# sensor-5.net
KiCad netlist of a schematic drawn in Altium Designer
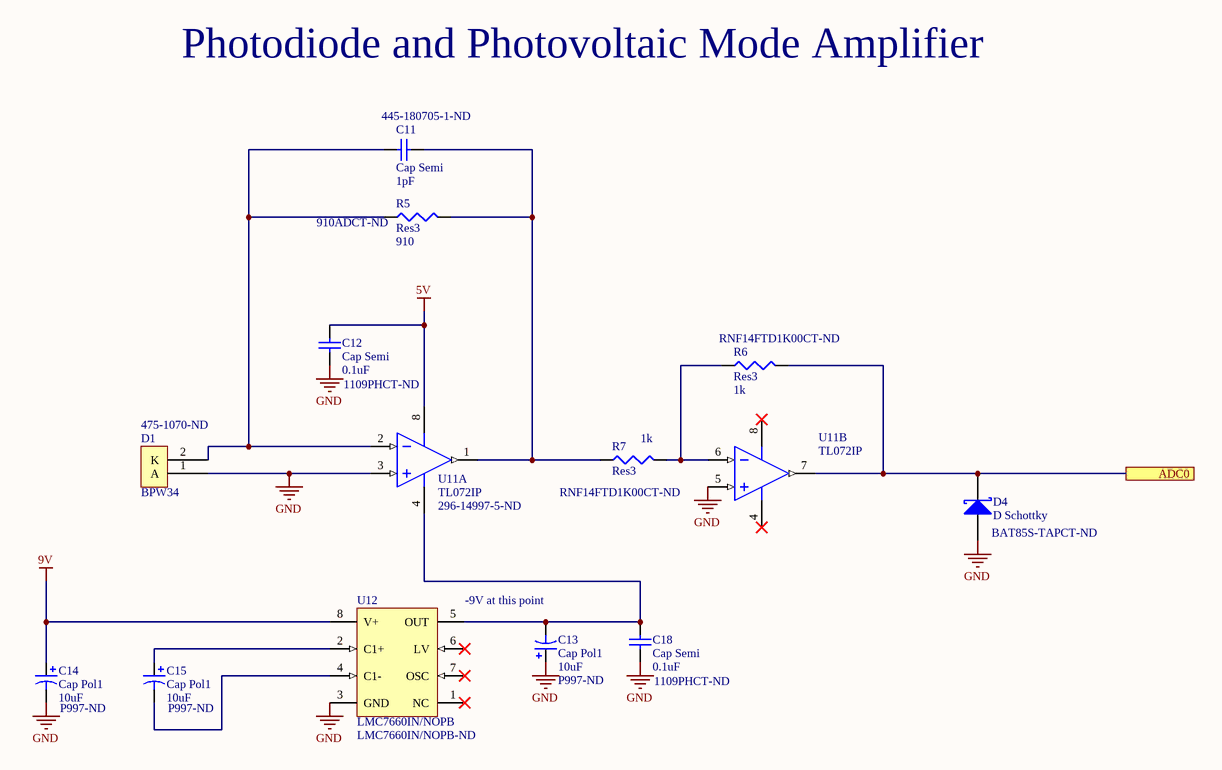
[diagram p0: sensor-5.SchDoc]

(export (version "E")
  (design (tool "Eeschema 10.0.6"))
  (components
    (comp (ref "C11")
      (value "Cap Semi")
      (footprint "FA28C0G1H010CNU06")
      (description "Capacitor (Semiconductor SIM Model)")
      (fields
        (field (name "ALTIUM_VALUE") "1pF")
        (field (name "SUPPLIER PART NUMBER 1") "445-180705-1-ND")
        (field (name "MANUFACTURER") "TDK")
        (field (name "MANUFACTURER PART NUMBER") "FA28C0G1H010CNU06")
        (field (name "PUBLISHER") "Altium Limited")
      )
      (libsource (lib "Miscellaneous Devices") (part "Cap Semi"))
    )
    (comp (ref "C12")
      (value "Cap Semi")
      (footprint "A104K15X7RF5TAA")
      (description "Capacitor (Semiconductor SIM Model)")
      (fields
        (field (name "ALTIUM_VALUE") "0.1uF")
        (field (name "SUPPLIER PART NUMBER 1") "1109PHCT-ND")
        (field (name "MANUFACTURER") "Vishay BCcomponents")
        (field (name "MANUFACTURER PART NUMBER") "A104K15X7RF5TAA")
        (field (name "PUBLISHER") "Altium Limited")
      )
      (libsource (lib "Miscellaneous Devices") (part "Cap Semi"))
    )
    (comp (ref "C13")
      (value "Cap Pol1")
      (footprint "ECE-A1HKS100")
      (description "Polarized Capacitor (Radial)")
      (fields
        (field (name "ALTIUM_VALUE") "10uF")
        (field (name "SUPPLIER PART NUMBER 1") "P997-ND")
        (field (name "MANUFACTURER") "Panasonic")
        (field (name "MANUFACTURER PART NUMBER") "ECE-A1HKS100")
        (field (name "PUBLISHER") "Altium Limited")
      )
      (libsource (lib "Miscellaneous Devices") (part "Cap Pol1"))
    )
    (comp (ref "C14")
      (value "Cap Pol1")
      (footprint "ECE-A1HKS100")
      (description "Polarized Capacitor (Radial)")
      (fields
        (field (name "ALTIUM_VALUE") "10uF")
        (field (name "SUPPLIER PART NUMBER 1") "P997-ND")
        (field (name "MANUFACTURER") "Panasonic")
        (field (name "MANUFACTURER PART NUMBER") "ECE-A1HKS100")
        (field (name "PUBLISHER") "Altium Limited")
      )
      (libsource (lib "Miscellaneous Devices") (part "Cap Pol1"))
    )
    (comp (ref "C15")
      (value "Cap Pol1")
      (footprint "ECE-A1HKS100")
      (description "Polarized Capacitor (Radial)")
      (fields
        (field (name "ALTIUM_VALUE") "10uF")
        (field (name "SUPPLIER PART NUMBER 1") "P997-ND")
        (field (name "MANUFACTURER") "Panasonic")
        (field (name "MANUFACTURER PART NUMBER") "ECE-A1HKS100")
        (field (name "PUBLISHER") "Altium Limited")
      )
      (libsource (lib "Miscellaneous Devices") (part "Cap Pol1"))
    )
    (comp (ref "C18")
      (value "Cap Semi")
      (footprint "A104K15X7RF5TAA")
      (description "Capacitor (Semiconductor SIM Model)")
      (fields
        (field (name "ALTIUM_VALUE") "0.1uF")
        (field (name "SUPPLIER PART NUMBER 1") "1109PHCT-ND")
        (field (name "MANUFACTURER") "Vishay BCcomponents")
        (field (name "MANUFACTURER PART NUMBER") "A104K15X7RF5TAA")
        (field (name "PUBLISHER") "Altium Limited")
      )
      (libsource (lib "Miscellaneous Devices") (part "Cap Semi"))
    )
    (comp (ref "D1")
      (value "BPW34")
      (footprint "BPW34")
      (fields
        (field (name "SUPPLIER PART NUMBER 1") "475-1070-ND")
        (field (name "MANUFACTURER") "Osram Opto")
      )
      (libsource (lib "osram") (part "BPW34"))
    )
    (comp (ref "D4")
      (value "D Schottky")
      (footprint "BAT85S-TAP")
      (description "Schottky Diode")
      (fields
        (field (name "SUPPLIER PART NUMBER 1") "BAT85S-TAPCT-ND")
        (field (name "MANUFACTURER") "Vishay")
        (field (name "MANUFACTURER PART NUMBER") "BAT85S-TAP")
        (field (name "PUBLISHER") "Altium Limited")
      )
      (libsource (lib "Miscellaneous Devices") (part "D Schottky"))
    )
    (comp (ref "R5")
      (value "Res3")
      (footprint "MFP-25BRD52-910R")
      (description "Resistor")
      (fields
        (field (name "ALTIUM_VALUE") "910")
        (field (name "SUPPLIER PART NUMBER 1") "910ADCT-ND")
        (field (name "MANUFACTURER") "Yageo")
        (field (name "MANUFACTURER PART NUMBER") "MFP-25BRD52-910R")
        (field (name "PUBLISHER") "Altium Limited")
      )
      (libsource (lib "Miscellaneous Devices") (part "Res3"))
    )
    (comp (ref "R6")
      (value "Res3")
      (footprint "RNF14FTD1K00")
      (description "Resistor")
      (fields
        (field (name "ALTIUM_VALUE") "1k")
        (field (name "SUPPLIER PART NUMBER 1") "RNF14FTD1K00CT-ND")
        (field (name "MANUFACTURER") "Stackpole Electronics")
        (field (name "MANUFACTURER PART NUMBER") "RNF14FTD1K00")
        (field (name "PUBLISHER") "Altium Limited")
      )
      (libsource (lib "Miscellaneous Devices") (part "Res3"))
    )
    (comp (ref "R7")
      (value "Res3")
      (footprint "RNF14FTD1K00")
      (description "Resistor")
      (fields
        (field (name "ALTIUM_VALUE") "1k")
        (field (name "SUPPLIER PART NUMBER 1") "RNF14FTD1K00CT-ND")
        (field (name "MANUFACTURER") "Stackpole Electronics")
        (field (name "MANUFACTURER PART NUMBER") "RNF14FTD1K00")
        (field (name "PUBLISHER") "Altium Limited")
      )
      (libsource (lib "Miscellaneous Devices") (part "Res3"))
    )
    (comp (ref "U11")
      (value "TL072IP")
      (footprint "P0008A")
      (fields
        (field (name "MANUFACTURER") "Texas Instruments")
        (field (name "SUPPLIER PART NUMBER 1") "296-14997-5-ND")
      )
      (libsource (lib "Altium Content Vault") (part "TI-AMP-D6-2-8_D"))
    )
    (comp (ref "U12")
      (value "LMC7660IN/NOPB")
      (footprint "P0008A")
      (description "Switched Capacitor Voltage Converter, 8-pin MDIP, Pb-Free")
      (fields
        (field (name "MANUFACTURER") "Texas Instruments")
        (field (name "SUPPLIER PART NUMBER 1") "LMC7660IN/NOPB-ND")
      )
      (libsource (lib "Altium Content Vault") (part "PM-CHP-LMC7660IM-8"))
    )
  )
  (nets
    (net (code "1") (name "/ADC0") (class "Default")
      (node (ref "D4") (pin "2") (pinfunction "K_2") (pintype "passive"))
      (node (ref "R6") (pin "2") (pinfunction "2_2") (pintype "passive"))
      (node (ref "U11") (pin "7") (pinfunction "OUT2_7") (pintype "output"))
    )
    (net (code "2") (name "5V") (class "Default")
      (node (ref "C12") (pin "2") (pinfunction "2_2") (pintype "passive"))
      (node (ref "U11") (pin "8") (pinfunction "VCC+_8") (pintype "power_in"))
    )
    (net (code "3") (name "9V") (class "Default")
      (node (ref "C14") (pin "1") (pinfunction "1_1") (pintype "passive"))
      (node (ref "U12") (pin "8") (pinfunction "V+_8") (pintype "power_in"))
    )
    (net (code "4") (name "GND") (class "Default")
      (node (ref "C12") (pin "1") (pinfunction "1_1") (pintype "passive"))
      (node (ref "C13") (pin "1") (pinfunction "1_1") (pintype "passive"))
      (node (ref "C14") (pin "2") (pinfunction "2_2") (pintype "passive"))
      (node (ref "C18") (pin "1") (pinfunction "1_1") (pintype "passive"))
      (node (ref "D1") (pin "1") (pinfunction "A_1") (pintype "passive"))
      (node (ref "D4") (pin "1") (pinfunction "A_1") (pintype "passive"))
      (node (ref "U11") (pin "3") (pinfunction "IN1+_3") (pintype "input"))
      (node (ref "U11") (pin "5") (pinfunction "IN2+_5") (pintype "input"))
      (node (ref "U12") (pin "3") (pinfunction "GND_3") (pintype "power_in"))
    )
    (net (code "5") (name "Net-(D1-K)") (class "Default")
      (node (ref "C11") (pin "1") (pinfunction "1_1") (pintype "passive"))
      (node (ref "D1") (pin "2") (pinfunction "K_2") (pintype "passive"))
      (node (ref "R5") (pin "1") (pinfunction "1_1") (pintype "passive"))
      (node (ref "U11") (pin "2") (pinfunction "IN1-_2") (pintype "input"))
    )
    (net (code "6") (name "Net-(U11A-OUT1)") (class "Default")
      (node (ref "C11") (pin "2") (pinfunction "2_2") (pintype "passive"))
      (node (ref "R5") (pin "2") (pinfunction "2_2") (pintype "passive"))
      (node (ref "R7") (pin "1") (pinfunction "1_1") (pintype "passive"))
      (node (ref "U11") (pin "1") (pinfunction "OUT1_1") (pintype "output"))
    )
    (net (code "7") (name "Net-(U11A-VCC-)") (class "Default")
      (node (ref "C13") (pin "2") (pinfunction "2_2") (pintype "passive"))
      (node (ref "C18") (pin "2") (pinfunction "2_2") (pintype "passive"))
      (node (ref "U11") (pin "4") (pinfunction "VCC-_4") (pintype "power_in"))
      (node (ref "U12") (pin "5") (pinfunction "OUT_5") (pintype "power_in"))
    )
    (net (code "8") (name "Net-(U11B-IN2-)") (class "Default")
      (node (ref "R6") (pin "1") (pinfunction "1_1") (pintype "passive"))
      (node (ref "R7") (pin "2") (pinfunction "2_2") (pintype "passive"))
      (node (ref "U11") (pin "6") (pinfunction "IN2-_6") (pintype "input"))
    )
    (net (code "9") (name "Net-(U12-C1+)") (class "Default")
      (node (ref "C15") (pin "1") (pinfunction "1_1") (pintype "passive"))
      (node (ref "U12") (pin "2") (pinfunction "C1+_2") (pintype "input"))
    )
    (net (code "10") (name "Net-(U12-C1-)") (class "Default")
      (node (ref "C15") (pin "2") (pinfunction "2_2") (pintype "passive"))
      (node (ref "U12") (pin "4") (pinfunction "C1-_4") (pintype "input"))
    )
    (net (code "11") (name "unconnected-(U11B-VCC+-Pad8)") (class "Default")
      (node (ref "U11") (pin "8") (pinfunction "VCC+_8") (pintype "power_in+no_connect"))
    )
    (net (code "12") (name "unconnected-(U11B-VCC--Pad4)") (class "Default")
      (node (ref "U11") (pin "4") (pinfunction "VCC-_4") (pintype "power_in+no_connect"))
    )
    (net (code "13") (name "unconnected-(U12-LV-Pad6)") (class "Default")
      (node (ref "U12") (pin "6") (pinfunction "LV_6") (pintype "input+no_connect"))
    )
    (net (code "14") (name "unconnected-(U12-NC-Pad1)") (class "Default")
      (node (ref "U12") (pin "1") (pinfunction "NC_1") (pintype "passive+no_connect"))
    )
    (net (code "15") (name "unconnected-(U12-OSC-Pad7)") (class "Default")
      (node (ref "U12") (pin "7") (pinfunction "OSC_7") (pintype "input+no_connect"))
    )
  )
)
